# CPU_PCB.net
KiCad netlist of a schematic drawn in Altium Designer
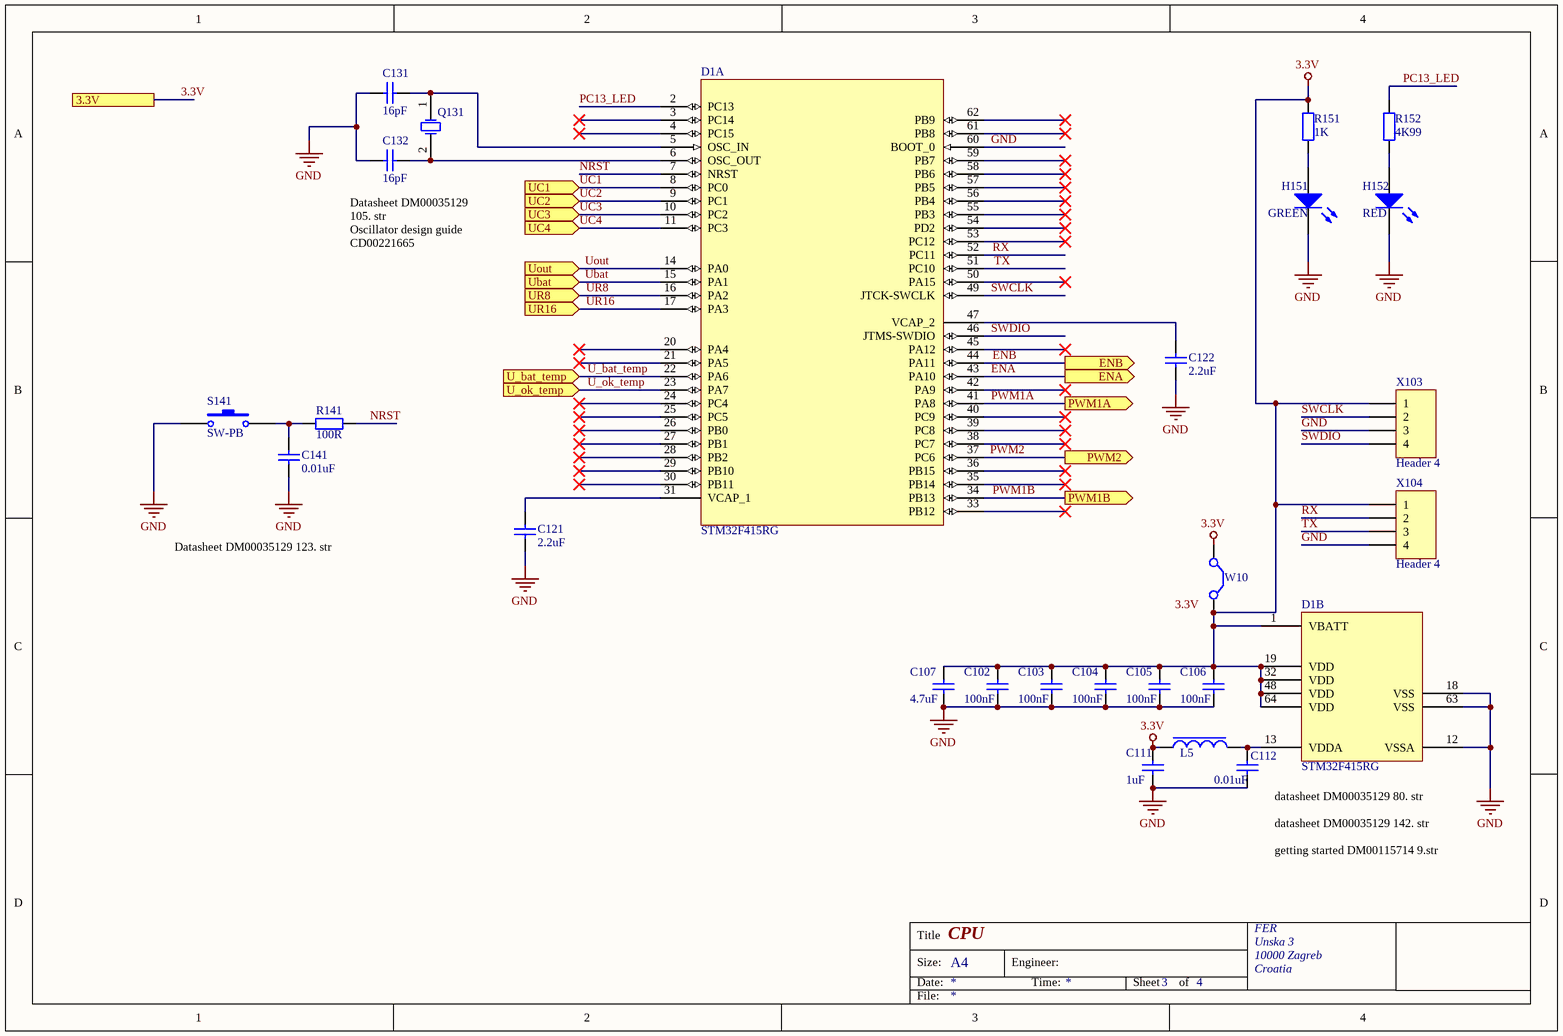
[diagram p0: CPU_PCB.SchDoc]

(export (version "E")
  (design (tool "Eeschema 10.0.6"))
  (components
    (comp (ref "C102")
      (value "100nF")
      (footprint "CAP_0805")
      (description "Capacitor")
      (libsource (lib "Miscellaneous Devices") (part "Cap"))
    )
    (comp (ref "C103")
      (value "100nF")
      (footprint "CAP_0805")
      (description "Capacitor")
      (libsource (lib "Miscellaneous Devices") (part "Cap"))
    )
    (comp (ref "C104")
      (value "100nF")
      (footprint "CAP_0805")
      (description "Capacitor")
      (libsource (lib "Miscellaneous Devices") (part "Cap"))
    )
    (comp (ref "C105")
      (value "100nF")
      (footprint "CAP_0805")
      (description "Capacitor")
      (libsource (lib "Miscellaneous Devices") (part "Cap"))
    )
    (comp (ref "C106")
      (value "100nF")
      (footprint "CAP_0805")
      (description "Capacitor")
      (libsource (lib "Miscellaneous Devices") (part "Cap"))
    )
    (comp (ref "C107")
      (value "4.7uF")
      (footprint "CAP_0805")
      (description "Capacitor")
      (libsource (lib "Miscellaneous Devices") (part "Cap"))
    )
    (comp (ref "C111")
      (value "1uF")
      (footprint "CAP_0805")
      (description "Capacitor")
      (libsource (lib "Miscellaneous Devices") (part "Cap"))
    )
    (comp (ref "C112")
      (value "0.01uF")
      (footprint "CAP_0603")
      (description "Capacitor")
      (libsource (lib "Miscellaneous Devices") (part "Cap"))
    )
    (comp (ref "C121")
      (value "2.2uF")
      (footprint "CAP_0805")
      (description "Capacitor")
      (libsource (lib "Miscellaneous Devices") (part "Cap"))
    )
    (comp (ref "C122")
      (value "2.2uF")
      (footprint "CAP_0805")
      (description "Capacitor")
      (libsource (lib "Miscellaneous Devices") (part "Cap"))
    )
    (comp (ref "C131")
      (value "16pF")
      (footprint "CAP_0603")
      (description "Capacitor")
      (libsource (lib "Miscellaneous Devices") (part "Cap"))
    )
    (comp (ref "C132")
      (value "16pF")
      (footprint "CAP_0603")
      (description "Capacitor")
      (libsource (lib "Miscellaneous Devices") (part "Cap"))
    )
    (comp (ref "C141")
      (value "0.01uF")
      (footprint "CAP_0603")
      (description "Capacitor")
      (libsource (lib "Miscellaneous Devices") (part "Cap"))
    )
    (comp (ref "D1")
      (value "STM32F415RG")
      (footprint "LQFP64")
      (description "Processor")
      (libsource (lib "CPU_Lib") (part "STM32F415RG"))
    )
    (comp (ref "H151")
      (value "GREEN")
      (footprint "LED 1.25X2 SMD")
      (description "Typical INFRARED GaAs LED")
      (libsource (lib "Miscellaneous Devices") (part "LED0"))
    )
    (comp (ref "H152")
      (value "RED")
      (footprint "LED 1.25X2 SMD")
      (description "Typical INFRARED GaAs LED")
      (libsource (lib "Miscellaneous Devices") (part "LED0"))
    )
    (comp (ref "L5")
      (value "Inductor")
      (footprint "C0805")
      (libsource (lib "Miscellaneous Devices") (part "Inductor"))
    )
    (comp (ref "Q131")
      (value "XTAL")
      (footprint "QUARTZ_SMD_16MHZ")
      (description "Crystal Oscillator")
      (libsource (lib "Miscellaneous Devices") (part "XTAL"))
    )
    (comp (ref "R141")
      (value "100R")
      (footprint "RES_0805")
      (description "Resistor")
      (libsource (lib "Miscellaneous Devices") (part "Res2"))
    )
    (comp (ref "R151")
      (value "1K")
      (footprint "RES_0603")
      (description "Resistor")
      (libsource (lib "") (part "Res2_1"))
    )
    (comp (ref "R152")
      (value "4K99")
      (footprint "RES_0805")
      (description "Resistor")
      (libsource (lib "") (part "Res2_1"))
    )
    (comp (ref "S141")
      (value "SW-PB")
      (footprint "SWITCH KSEK43GLFS")
      (description "Switch")
      (libsource (lib "Miscellaneous Devices") (part "SW-PB"))
    )
    (comp (ref "W10")
      (value "Jumper")
      (footprint "HDR1X2")
      (description "Jumper Wire")
      (libsource (lib "Miscellaneous Devices") (part "Jumper"))
    )
    (comp (ref "X103")
      (value "Header 4")
      (footprint "HEADER-4_PIN")
      (description "Header, 4-Pin")
      (libsource (lib "Miscellaneous Connectors") (part "Header 4"))
    )
    (comp (ref "X104")
      (value "Header 4")
      (footprint "HEADER-4_PIN")
      (description "Header, 4-Pin")
      (libsource (lib "Miscellaneous Connectors") (part "Header 4"))
    )
  )
  (nets
    (net (code "1") (name "/ENA") (class "Default")
      (node (ref "D1") (pin "43") (pinfunction "PA10_43") (pintype "bidirectional"))
    )
    (net (code "2") (name "/ENB") (class "Default")
      (node (ref "D1") (pin "44") (pinfunction "PA11_44") (pintype "bidirectional"))
    )
    (net (code "3") (name "/NRST") (class "Default")
      (node (ref "D1") (pin "7") (pinfunction "NRST_7") (pintype "bidirectional"))
      (node (ref "R141") (pin "1") (pinfunction "1_1") (pintype "passive"))
    )
    (net (code "4") (name "/PC13_LED") (class "Default")
      (node (ref "D1") (pin "2") (pinfunction "PC13_2") (pintype "bidirectional"))
      (node (ref "R152") (pin "2") (pinfunction "2_2") (pintype "passive"))
    )
    (net (code "5") (name "/PWM1A") (class "Default")
      (node (ref "D1") (pin "41") (pinfunction "PA8_41") (pintype "bidirectional"))
    )
    (net (code "6") (name "/PWM1B") (class "Default")
      (node (ref "D1") (pin "34") (pinfunction "PB13_34") (pintype "bidirectional"))
    )
    (net (code "7") (name "/PWM2") (class "Default")
      (node (ref "D1") (pin "37") (pinfunction "PC6_37") (pintype "bidirectional"))
    )
    (net (code "8") (name "/RX") (class "Default")
      (node (ref "D1") (pin "52") (pinfunction "PC11_52") (pintype "bidirectional"))
      (node (ref "X104") (pin "2") (pinfunction "2_2") (pintype "passive"))
    )
    (net (code "9") (name "/SWCLK") (class "Default")
      (node (ref "D1") (pin "49") (pinfunction "JTCK-SWCLK_49") (pintype "bidirectional"))
      (node (ref "X103") (pin "2") (pinfunction "2_2") (pintype "passive"))
    )
    (net (code "10") (name "/SWDIO") (class "Default")
      (node (ref "D1") (pin "46") (pinfunction "JTMS-SWDIO_46") (pintype "bidirectional"))
      (node (ref "X103") (pin "4") (pinfunction "4_4") (pintype "passive"))
    )
    (net (code "11") (name "/TX") (class "Default")
      (node (ref "D1") (pin "51") (pinfunction "PC10_51") (pintype "bidirectional"))
      (node (ref "X104") (pin "3") (pinfunction "3_3") (pintype "passive"))
    )
    (net (code "12") (name "/UC1") (class "Default")
      (node (ref "D1") (pin "8") (pinfunction "PC0_8") (pintype "bidirectional"))
    )
    (net (code "13") (name "/UC2") (class "Default")
      (node (ref "D1") (pin "9") (pinfunction "PC1_9") (pintype "bidirectional"))
    )
    (net (code "14") (name "/UC3") (class "Default")
      (node (ref "D1") (pin "10") (pinfunction "PC2_10") (pintype "bidirectional"))
    )
    (net (code "15") (name "/UC4") (class "Default")
      (node (ref "D1") (pin "11") (pinfunction "PC3_11") (pintype "bidirectional"))
    )
    (net (code "16") (name "/UR8") (class "Default")
      (node (ref "D1") (pin "16") (pinfunction "PA2_16") (pintype "bidirectional"))
    )
    (net (code "17") (name "/UR16") (class "Default")
      (node (ref "D1") (pin "17") (pinfunction "PA3_17") (pintype "bidirectional"))
    )
    (net (code "18") (name "/U_bat_temp") (class "Default")
      (node (ref "D1") (pin "22") (pinfunction "PA6_22") (pintype "bidirectional"))
    )
    (net (code "19") (name "/U_ok_temp") (class "Default")
      (node (ref "D1") (pin "23") (pinfunction "PA7_23") (pintype "bidirectional"))
    )
    (net (code "20") (name "/Ubat") (class "Default")
      (node (ref "D1") (pin "15") (pinfunction "PA1_15") (pintype "bidirectional"))
    )
    (net (code "21") (name "/Uout") (class "Default")
      (node (ref "D1") (pin "14") (pinfunction "PA0_14") (pintype "bidirectional"))
    )
    (net (code "22") (name "3.3V") (class "Default")
      (node (ref "C102") (pin "2") (pinfunction "2_2") (pintype "passive"))
      (node (ref "C103") (pin "2") (pinfunction "2_2") (pintype "passive"))
      (node (ref "C104") (pin "2") (pinfunction "2_2") (pintype "passive"))
      (node (ref "C105") (pin "2") (pinfunction "2_2") (pintype "passive"))
      (node (ref "C106") (pin "2") (pinfunction "2_2") (pintype "passive"))
      (node (ref "C107") (pin "2") (pinfunction "2_2") (pintype "passive"))
      (node (ref "C111") (pin "2") (pinfunction "2_2") (pintype "passive"))
      (node (ref "D1") (pin "1") (pinfunction "VBATT_1") (pintype "passive"))
      (node (ref "D1") (pin "19") (pinfunction "VDD_19") (pintype "power_in"))
      (node (ref "D1") (pin "32") (pinfunction "VDD_32") (pintype "power_in"))
      (node (ref "D1") (pin "48") (pinfunction "VDD_48") (pintype "power_in"))
      (node (ref "D1") (pin "64") (pinfunction "VDD_64") (pintype "power_in"))
      (node (ref "L5") (pin "1") (pinfunction "1_1") (pintype "passive"))
      (node (ref "R151") (pin "2") (pinfunction "2_2") (pintype "passive"))
      (node (ref "W10") (pin "1") (pinfunction "C1_1") (pintype "passive"))
      (node (ref "W10") (pin "2") (pinfunction "C2_2") (pintype "passive"))
      (node (ref "X103") (pin "1") (pinfunction "1_1") (pintype "passive"))
      (node (ref "X104") (pin "1") (pinfunction "1_1") (pintype "passive"))
    )
    (net (code "23") (name "GND") (class "Default")
      (node (ref "C102") (pin "1") (pinfunction "1_1") (pintype "passive"))
      (node (ref "C103") (pin "1") (pinfunction "1_1") (pintype "passive"))
      (node (ref "C104") (pin "1") (pinfunction "1_1") (pintype "passive"))
      (node (ref "C105") (pin "1") (pinfunction "1_1") (pintype "passive"))
      (node (ref "C106") (pin "1") (pinfunction "1_1") (pintype "passive"))
      (node (ref "C107") (pin "1") (pinfunction "1_1") (pintype "passive"))
      (node (ref "C111") (pin "1") (pinfunction "1_1") (pintype "passive"))
      (node (ref "C112") (pin "1") (pinfunction "1_1") (pintype "passive"))
      (node (ref "C121") (pin "1") (pinfunction "1_1") (pintype "passive"))
      (node (ref "C122") (pin "1") (pinfunction "1_1") (pintype "passive"))
      (node (ref "C131") (pin "2") (pinfunction "2_2") (pintype "passive"))
      (node (ref "C132") (pin "2") (pinfunction "2_2") (pintype "passive"))
      (node (ref "C141") (pin "1") (pinfunction "1_1") (pintype "passive"))
      (node (ref "D1") (pin "12") (pinfunction "VSSA_12") (pintype "power_in"))
      (node (ref "D1") (pin "18") (pinfunction "VSS_18") (pintype "power_in"))
      (node (ref "D1") (pin "60") (pinfunction "BOOT_0_60") (pintype "input"))
      (node (ref "D1") (pin "63") (pinfunction "VSS_63") (pintype "power_in"))
      (node (ref "H151") (pin "2") (pinfunction "K_2") (pintype "passive"))
      (node (ref "H152") (pin "2") (pinfunction "K_2") (pintype "passive"))
      (node (ref "S141") (pin "2") (pinfunction "2_2") (pintype "passive"))
      (node (ref "X103") (pin "3") (pinfunction "3_3") (pintype "passive"))
      (node (ref "X104") (pin "4") (pinfunction "4_4") (pintype "passive"))
    )
    (net (code "24") (name "Net-(C141-Pad2)") (class "Default")
      (node (ref "C141") (pin "2") (pinfunction "2_2") (pintype "passive"))
      (node (ref "R141") (pin "2") (pinfunction "2_2") (pintype "passive"))
      (node (ref "S141") (pin "1") (pinfunction "1_1") (pintype "passive"))
    )
    (net (code "25") (name "Net-(D1A-OSC_IN)") (class "Default")
      (node (ref "C131") (pin "1") (pinfunction "1_1") (pintype "passive"))
      (node (ref "D1") (pin "5") (pinfunction "OSC_IN_5") (pintype "input"))
      (node (ref "Q131") (pin "1") (pinfunction "OSC1_1") (pintype "passive"))
    )
    (net (code "26") (name "Net-(D1A-OSC_OUT)") (class "Default")
      (node (ref "C132") (pin "1") (pinfunction "1_1") (pintype "passive"))
      (node (ref "D1") (pin "6") (pinfunction "OSC_OUT_6") (pintype "bidirectional"))
      (node (ref "Q131") (pin "2") (pinfunction "OSC2_2") (pintype "passive"))
    )
    (net (code "27") (name "Net-(D1A-VCAP_1)") (class "Default")
      (node (ref "C121") (pin "2") (pinfunction "2_2") (pintype "passive"))
      (node (ref "D1") (pin "31") (pinfunction "VCAP_1_31") (pintype "power_in"))
    )
    (net (code "28") (name "Net-(D1A-VCAP_2)") (class "Default")
      (node (ref "C122") (pin "2") (pinfunction "2_2") (pintype "passive"))
      (node (ref "D1") (pin "47") (pinfunction "VCAP_2_47") (pintype "power_in"))
    )
    (net (code "29") (name "Net-(D1B-VDDA)") (class "Default")
      (node (ref "C112") (pin "2") (pinfunction "2_2") (pintype "passive"))
      (node (ref "D1") (pin "13") (pinfunction "VDDA_13") (pintype "power_in"))
      (node (ref "L5") (pin "2") (pinfunction "2_2") (pintype "passive"))
    )
    (net (code "30") (name "Net-(H151-A)") (class "Default")
      (node (ref "H151") (pin "1") (pinfunction "A_1") (pintype "passive"))
      (node (ref "R151") (pin "1") (pinfunction "1_1") (pintype "passive"))
    )
    (net (code "31") (name "Net-(H152-A)") (class "Default")
      (node (ref "H152") (pin "1") (pinfunction "A_1") (pintype "passive"))
      (node (ref "R152") (pin "1") (pinfunction "1_1") (pintype "passive"))
    )
    (net (code "32") (name "unconnected-(D1A-PA4-Pad20)") (class "Default")
      (node (ref "D1") (pin "20") (pinfunction "PA4_20") (pintype "bidirectional+no_connect"))
    )
    (net (code "33") (name "unconnected-(D1A-PA5-Pad21)") (class "Default")
      (node (ref "D1") (pin "21") (pinfunction "PA5_21") (pintype "bidirectional+no_connect"))
    )
    (net (code "34") (name "unconnected-(D1A-PA9-Pad42)") (class "Default")
      (node (ref "D1") (pin "42") (pinfunction "PA9_42") (pintype "bidirectional+no_connect"))
    )
    (net (code "35") (name "unconnected-(D1A-PA12-Pad45)") (class "Default")
      (node (ref "D1") (pin "45") (pinfunction "PA12_45") (pintype "bidirectional+no_connect"))
    )
    (net (code "36") (name "unconnected-(D1A-PA15-Pad50)") (class "Default")
      (node (ref "D1") (pin "50") (pinfunction "PA15_50") (pintype "bidirectional+no_connect"))
    )
    (net (code "37") (name "unconnected-(D1A-PB0-Pad26)") (class "Default")
      (node (ref "D1") (pin "26") (pinfunction "PB0_26") (pintype "bidirectional+no_connect"))
    )
    (net (code "38") (name "unconnected-(D1A-PB1-Pad27)") (class "Default")
      (node (ref "D1") (pin "27") (pinfunction "PB1_27") (pintype "bidirectional+no_connect"))
    )
    (net (code "39") (name "unconnected-(D1A-PB2-Pad28)") (class "Default")
      (node (ref "D1") (pin "28") (pinfunction "PB2_28") (pintype "bidirectional+no_connect"))
    )
    (net (code "40") (name "unconnected-(D1A-PB3-Pad55)") (class "Default")
      (node (ref "D1") (pin "55") (pinfunction "PB3_55") (pintype "bidirectional+no_connect"))
    )
    (net (code "41") (name "unconnected-(D1A-PB4-Pad56)") (class "Default")
      (node (ref "D1") (pin "56") (pinfunction "PB4_56") (pintype "bidirectional+no_connect"))
    )
    (net (code "42") (name "unconnected-(D1A-PB5-Pad57)") (class "Default")
      (node (ref "D1") (pin "57") (pinfunction "PB5_57") (pintype "bidirectional+no_connect"))
    )
    (net (code "43") (name "unconnected-(D1A-PB6-Pad58)") (class "Default")
      (node (ref "D1") (pin "58") (pinfunction "PB6_58") (pintype "bidirectional+no_connect"))
    )
    (net (code "44") (name "unconnected-(D1A-PB7-Pad59)") (class "Default")
      (node (ref "D1") (pin "59") (pinfunction "PB7_59") (pintype "bidirectional+no_connect"))
    )
    (net (code "45") (name "unconnected-(D1A-PB8-Pad61)") (class "Default")
      (node (ref "D1") (pin "61") (pinfunction "PB8_61") (pintype "bidirectional+no_connect"))
    )
    (net (code "46") (name "unconnected-(D1A-PB9-Pad62)") (class "Default")
      (node (ref "D1") (pin "62") (pinfunction "PB9_62") (pintype "bidirectional+no_connect"))
    )
    (net (code "47") (name "unconnected-(D1A-PB10-Pad29)") (class "Default")
      (node (ref "D1") (pin "29") (pinfunction "PB10_29") (pintype "bidirectional+no_connect"))
    )
    (net (code "48") (name "unconnected-(D1A-PB11-Pad30)") (class "Default")
      (node (ref "D1") (pin "30") (pinfunction "PB11_30") (pintype "bidirectional+no_connect"))
    )
    (net (code "49") (name "unconnected-(D1A-PB12-Pad33)") (class "Default")
      (node (ref "D1") (pin "33") (pinfunction "PB12_33") (pintype "bidirectional+no_connect"))
    )
    (net (code "50") (name "unconnected-(D1A-PB14-Pad35)") (class "Default")
      (node (ref "D1") (pin "35") (pinfunction "PB14_35") (pintype "bidirectional+no_connect"))
    )
    (net (code "51") (name "unconnected-(D1A-PB15-Pad36)") (class "Default")
      (node (ref "D1") (pin "36") (pinfunction "PB15_36") (pintype "bidirectional+no_connect"))
    )
    (net (code "52") (name "unconnected-(D1A-PC4-Pad24)") (class "Default")
      (node (ref "D1") (pin "24") (pinfunction "PC4_24") (pintype "bidirectional+no_connect"))
    )
    (net (code "53") (name "unconnected-(D1A-PC5-Pad25)") (class "Default")
      (node (ref "D1") (pin "25") (pinfunction "PC5_25") (pintype "bidirectional+no_connect"))
    )
    (net (code "54") (name "unconnected-(D1A-PC7-Pad38)") (class "Default")
      (node (ref "D1") (pin "38") (pinfunction "PC7_38") (pintype "bidirectional+no_connect"))
    )
    (net (code "55") (name "unconnected-(D1A-PC8-Pad39)") (class "Default")
      (node (ref "D1") (pin "39") (pinfunction "PC8_39") (pintype "bidirectional+no_connect"))
    )
    (net (code "56") (name "unconnected-(D1A-PC9-Pad40)") (class "Default")
      (node (ref "D1") (pin "40") (pinfunction "PC9_40") (pintype "bidirectional+no_connect"))
    )
    (net (code "57") (name "unconnected-(D1A-PC12-Pad53)") (class "Default")
      (node (ref "D1") (pin "53") (pinfunction "PC12_53") (pintype "bidirectional+no_connect"))
    )
    (net (code "58") (name "unconnected-(D1A-PC14-Pad3)") (class "Default")
      (node (ref "D1") (pin "3") (pinfunction "PC14_3") (pintype "bidirectional+no_connect"))
    )
    (net (code "59") (name "unconnected-(D1A-PC15-Pad4)") (class "Default")
      (node (ref "D1") (pin "4") (pinfunction "PC15_4") (pintype "bidirectional+no_connect"))
    )
    (net (code "60") (name "unconnected-(D1A-PD2-Pad54)") (class "Default")
      (node (ref "D1") (pin "54") (pinfunction "PD2_54") (pintype "bidirectional+no_connect"))
    )
  )
)
